# Sheet1.net
KiCad netlist of a schematic drawn in Altium Designer
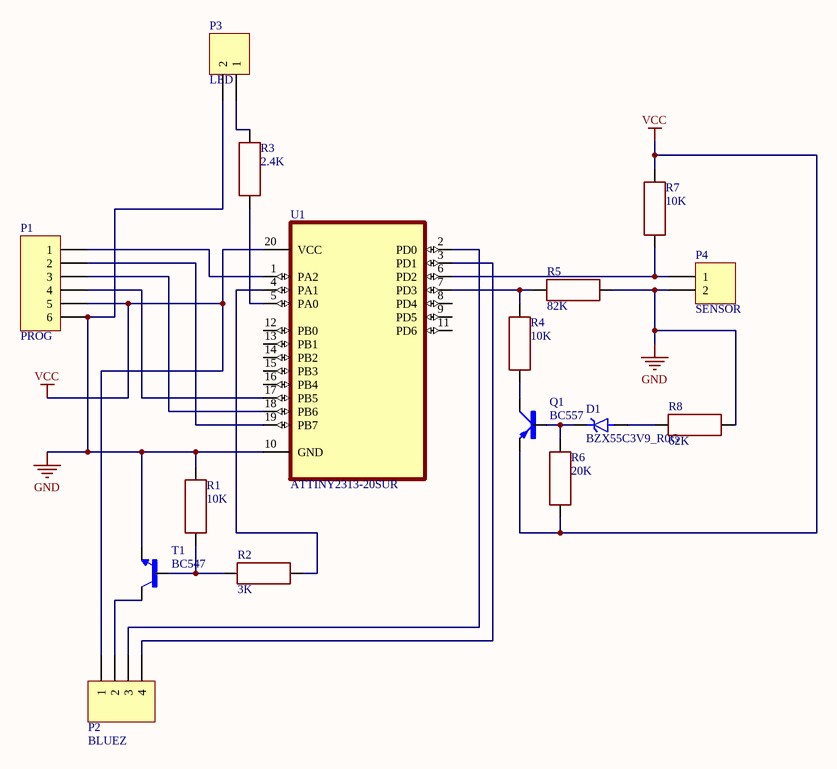
[diagram p0: Sheet1.SchDoc]

(export (version "E")
  (design (tool "Eeschema 10.0.6"))
  (components
    (comp (ref "D1")
      (value "BZX55C3V9_R0G")
      (footprint "DIOAD928W47L399D179")
      (fields (field (name "MP") "altium_native_batch"))
      (libsource (lib "BZX55C3V9_R0G") (part "BZX55C3V9_R0G"))
    )
    (comp (ref "P1")
      (value "PROG")
      (footprint "HDR1X6")
      (description "Header, 6-Pin")
      (fields (field (name "PUBLISHER") "Altium Limited"))
      (libsource (lib "Miscellaneous Connectors") (part "Header 6"))
    )
    (comp (ref "P2")
      (value "BLUEZ")
      (footprint "HDR1X4")
      (description "Header, 4-Pin")
      (fields (field (name "PUBLISHER") "Altium Limited"))
      (libsource (lib "Miscellaneous Connectors") (part "Header 4"))
    )
    (comp (ref "P3")
      (value "LED")
      (footprint "HDR1X2")
      (description "Header, 2-Pin")
      (fields (field (name "PUBLISHER") "Altium Limited"))
      (libsource (lib "Miscellaneous Connectors") (part "Header 2"))
    )
    (comp (ref "P4")
      (value "SENSOR")
      (footprint "HDR1X2")
      (description "Header, 2-Pin")
      (fields (field (name "PUBLISHER") "Altium Limited"))
      (libsource (lib "Miscellaneous Connectors") (part "Header 2"))
    )
    (comp (ref "Q1")
      (value "BC557")
      (footprint "SOT54A")
      (description "Bipolar (BJT) Transistor PNP 45 V 100 mA 320MHz 625 mW Through Hole TO-92 (TO-226)")
      (fields (field (name "MF") "ON Semiconductor"))
      (libsource (lib "BC557") (part "BC557"))
    )
    (comp (ref "R1") (value "10K") (footprint "RES 0805") (libsource (lib "") (part "RES_1")))
    (comp (ref "R2") (value "3K") (footprint "RES 0805") (libsource (lib "Schlib1") (part "RES")))
    (comp (ref "R3") (value "2.4K") (footprint "RES 0805") (libsource (lib "") (part "RES_1")))
    (comp (ref "R4") (value "10K") (footprint "RES 0805") (libsource (lib "") (part "RES_1")))
    (comp (ref "R5") (value "82K") (footprint "RES 0805") (libsource (lib "Schlib1") (part "RES")))
    (comp (ref "R6") (value "20K") (footprint "RES 0805") (libsource (lib "") (part "RES_1")))
    (comp (ref "R7") (value "10K") (footprint "RES 0805") (libsource (lib "") (part "RES_1")))
    (comp (ref "R8") (value "62K") (footprint "RES 0805") (libsource (lib "Schlib1") (part "RES")))
    (comp (ref "T1")
      (value "BC547")
      (footprint "TO92")
      (description "Trans GP BJT NPN 45V 0.1A 500mW 3-Pin TO-92 T/R")
      (fields (field (name "MF") "ON Semiconductor"))
      (libsource (lib "BC547") (part "BC547"))
    )
    (comp (ref "U1")
      (value "ATTINY2313-20SUR")
      (footprint "SOIC127P1032X265-20N")
      (description "AVR series Microcontroller IC 8-Bit 20MHz 2KB (1K x 16) FLASH 20-SOIC")
      (fields (field (name "MF") "Microchip Technology"))
      (libsource (lib "ATTINY2313-20SUR") (part "ATTINY2313-20SUR"))
    )
  )
  (nets
    (net (code "1") (name "GND") (class "Default")
      (node (ref "P1") (pin "6") (pinfunction "6_6") (pintype "passive"))
      (node (ref "P3") (pin "2") (pinfunction "2_2") (pintype "passive"))
      (node (ref "P4") (pin "2") (pinfunction "2_2") (pintype "passive"))
      (node (ref "R1") (pin "2") (pinfunction "2_2") (pintype "passive"))
      (node (ref "R5") (pin "2") (pinfunction "2_2") (pintype "passive"))
      (node (ref "R8") (pin "2") (pinfunction "2_2") (pintype "passive"))
      (node (ref "T1") (pin "1") (pinfunction "E_1") (pintype "passive"))
      (node (ref "U1") (pin "10") (pinfunction "GND_10") (pintype "passive"))
    )
    (net (code "2") (name "Net-(D1-K)") (class "Default")
      (node (ref "D1") (pin "C") (pinfunction "K_C") (pintype "passive"))
      (node (ref "Q1") (pin "B") (pinfunction "B_B") (pintype "passive"))
      (node (ref "R6") (pin "2") (pinfunction "2_2") (pintype "passive"))
    )
    (net (code "3") (name "Net-(D1-PadA)") (class "Default")
      (node (ref "D1") (pin "A") (pinfunction "A_A") (pintype "passive"))
      (node (ref "R8") (pin "1") (pinfunction "1_1") (pintype "passive"))
    )
    (net (code "4") (name "Net-(P3-Pad1)") (class "Default")
      (node (ref "P3") (pin "1") (pinfunction "1_1") (pintype "passive"))
      (node (ref "R3") (pin "2") (pinfunction "2_2") (pintype "passive"))
    )
    (net (code "5") (name "Net-(Q1-PadC)") (class "Default")
      (node (ref "Q1") (pin "C") (pinfunction "C_C") (pintype "passive"))
      (node (ref "R4") (pin "1") (pinfunction "1_1") (pintype "passive"))
    )
    (net (code "6") (name "Net-(T1-B)") (class "Default")
      (node (ref "R1") (pin "1") (pinfunction "1_1") (pintype "passive"))
      (node (ref "R2") (pin "1") (pinfunction "1_1") (pintype "passive"))
      (node (ref "T1") (pin "2") (pinfunction "B_2") (pintype "passive"))
    )
    (net (code "7") (name "Net-(T1-C)") (class "Default")
      (node (ref "P2") (pin "2") (pinfunction "2_2") (pintype "passive"))
      (node (ref "T1") (pin "3") (pinfunction "C_3") (pintype "passive"))
    )
    (net (code "8") (name "Net-(U1-PA0)") (class "Default")
      (node (ref "R3") (pin "1") (pinfunction "1_1") (pintype "passive"))
      (node (ref "U1") (pin "5") (pinfunction "PA0_5") (pintype "bidirectional"))
    )
    (net (code "9") (name "Net-(U1-PA1)") (class "Default")
      (node (ref "R2") (pin "2") (pinfunction "2_2") (pintype "passive"))
      (node (ref "U1") (pin "4") (pinfunction "PA1_4") (pintype "bidirectional"))
    )
    (net (code "10") (name "Net-(U1-PA2)") (class "Default")
      (node (ref "P1") (pin "1") (pinfunction "1_1") (pintype "passive"))
      (node (ref "U1") (pin "1") (pinfunction "PA2_1") (pintype "bidirectional"))
    )
    (net (code "11") (name "Net-(U1-PB5)") (class "Default")
      (node (ref "P1") (pin "4") (pinfunction "4_4") (pintype "passive"))
      (node (ref "U1") (pin "17") (pinfunction "PB5_17") (pintype "bidirectional"))
    )
    (net (code "12") (name "Net-(U1-PB6)") (class "Default")
      (node (ref "P1") (pin "3") (pinfunction "3_3") (pintype "passive"))
      (node (ref "U1") (pin "18") (pinfunction "PB6_18") (pintype "bidirectional"))
    )
    (net (code "13") (name "Net-(U1-PB7)") (class "Default")
      (node (ref "P1") (pin "2") (pinfunction "2_2") (pintype "passive"))
      (node (ref "U1") (pin "19") (pinfunction "PB7_19") (pintype "bidirectional"))
    )
    (net (code "14") (name "Net-(U1-PD0)") (class "Default")
      (node (ref "P2") (pin "3") (pinfunction "3_3") (pintype "passive"))
      (node (ref "U1") (pin "2") (pinfunction "PD0_2") (pintype "bidirectional"))
    )
    (net (code "15") (name "Net-(U1-PD1)") (class "Default")
      (node (ref "P2") (pin "4") (pinfunction "4_4") (pintype "passive"))
      (node (ref "U1") (pin "3") (pinfunction "PD1_3") (pintype "bidirectional"))
    )
    (net (code "16") (name "Net-(U1-PD2)") (class "Default")
      (node (ref "P4") (pin "1") (pinfunction "1_1") (pintype "passive"))
      (node (ref "R7") (pin "1") (pinfunction "1_1") (pintype "passive"))
      (node (ref "U1") (pin "6") (pinfunction "PD2_6") (pintype "bidirectional"))
    )
    (net (code "17") (name "Net-(U1-PD3)") (class "Default")
      (node (ref "R4") (pin "2") (pinfunction "2_2") (pintype "passive"))
      (node (ref "R5") (pin "1") (pinfunction "1_1") (pintype "passive"))
      (node (ref "U1") (pin "7") (pinfunction "PD3_7") (pintype "bidirectional"))
    )
    (net (code "18") (name "VCC") (class "Default")
      (node (ref "P1") (pin "5") (pinfunction "5_5") (pintype "passive"))
      (node (ref "P2") (pin "1") (pinfunction "1_1") (pintype "passive"))
      (node (ref "Q1") (pin "E") (pinfunction "E_E") (pintype "passive"))
      (node (ref "R6") (pin "1") (pinfunction "1_1") (pintype "passive"))
      (node (ref "R7") (pin "2") (pinfunction "2_2") (pintype "passive"))
      (node (ref "U1") (pin "20") (pinfunction "VCC_20") (pintype "power_in"))
    )
    (net (code "19") (name "unconnected-(U1-PB0-Pad12)") (class "Default")
      (node (ref "U1") (pin "12") (pinfunction "PB0_12") (pintype "bidirectional"))
    )
    (net (code "20") (name "unconnected-(U1-PB1-Pad13)") (class "Default")
      (node (ref "U1") (pin "13") (pinfunction "PB1_13") (pintype "bidirectional"))
    )
    (net (code "21") (name "unconnected-(U1-PB2-Pad14)") (class "Default")
      (node (ref "U1") (pin "14") (pinfunction "PB2_14") (pintype "bidirectional"))
    )
    (net (code "22") (name "unconnected-(U1-PB3-Pad15)") (class "Default")
      (node (ref "U1") (pin "15") (pinfunction "PB3_15") (pintype "bidirectional"))
    )
    (net (code "23") (name "unconnected-(U1-PB4-Pad16)") (class "Default")
      (node (ref "U1") (pin "16") (pinfunction "PB4_16") (pintype "bidirectional"))
    )
    (net (code "24") (name "unconnected-(U1-PD4-Pad8)") (class "Default")
      (node (ref "U1") (pin "8") (pinfunction "PD4_8") (pintype "bidirectional"))
    )
    (net (code "25") (name "unconnected-(U1-PD5-Pad9)") (class "Default")
      (node (ref "U1") (pin "9") (pinfunction "PD5_9") (pintype "bidirectional"))
    )
    (net (code "26") (name "unconnected-(U1-PD6-Pad11)") (class "Default")
      (node (ref "U1") (pin "11") (pinfunction "PD6_11") (pintype "bidirectional"))
    )
  )
)
